# Danger_Shield-v17.net
KiCad netlist of a schematic drawn in EAGLE
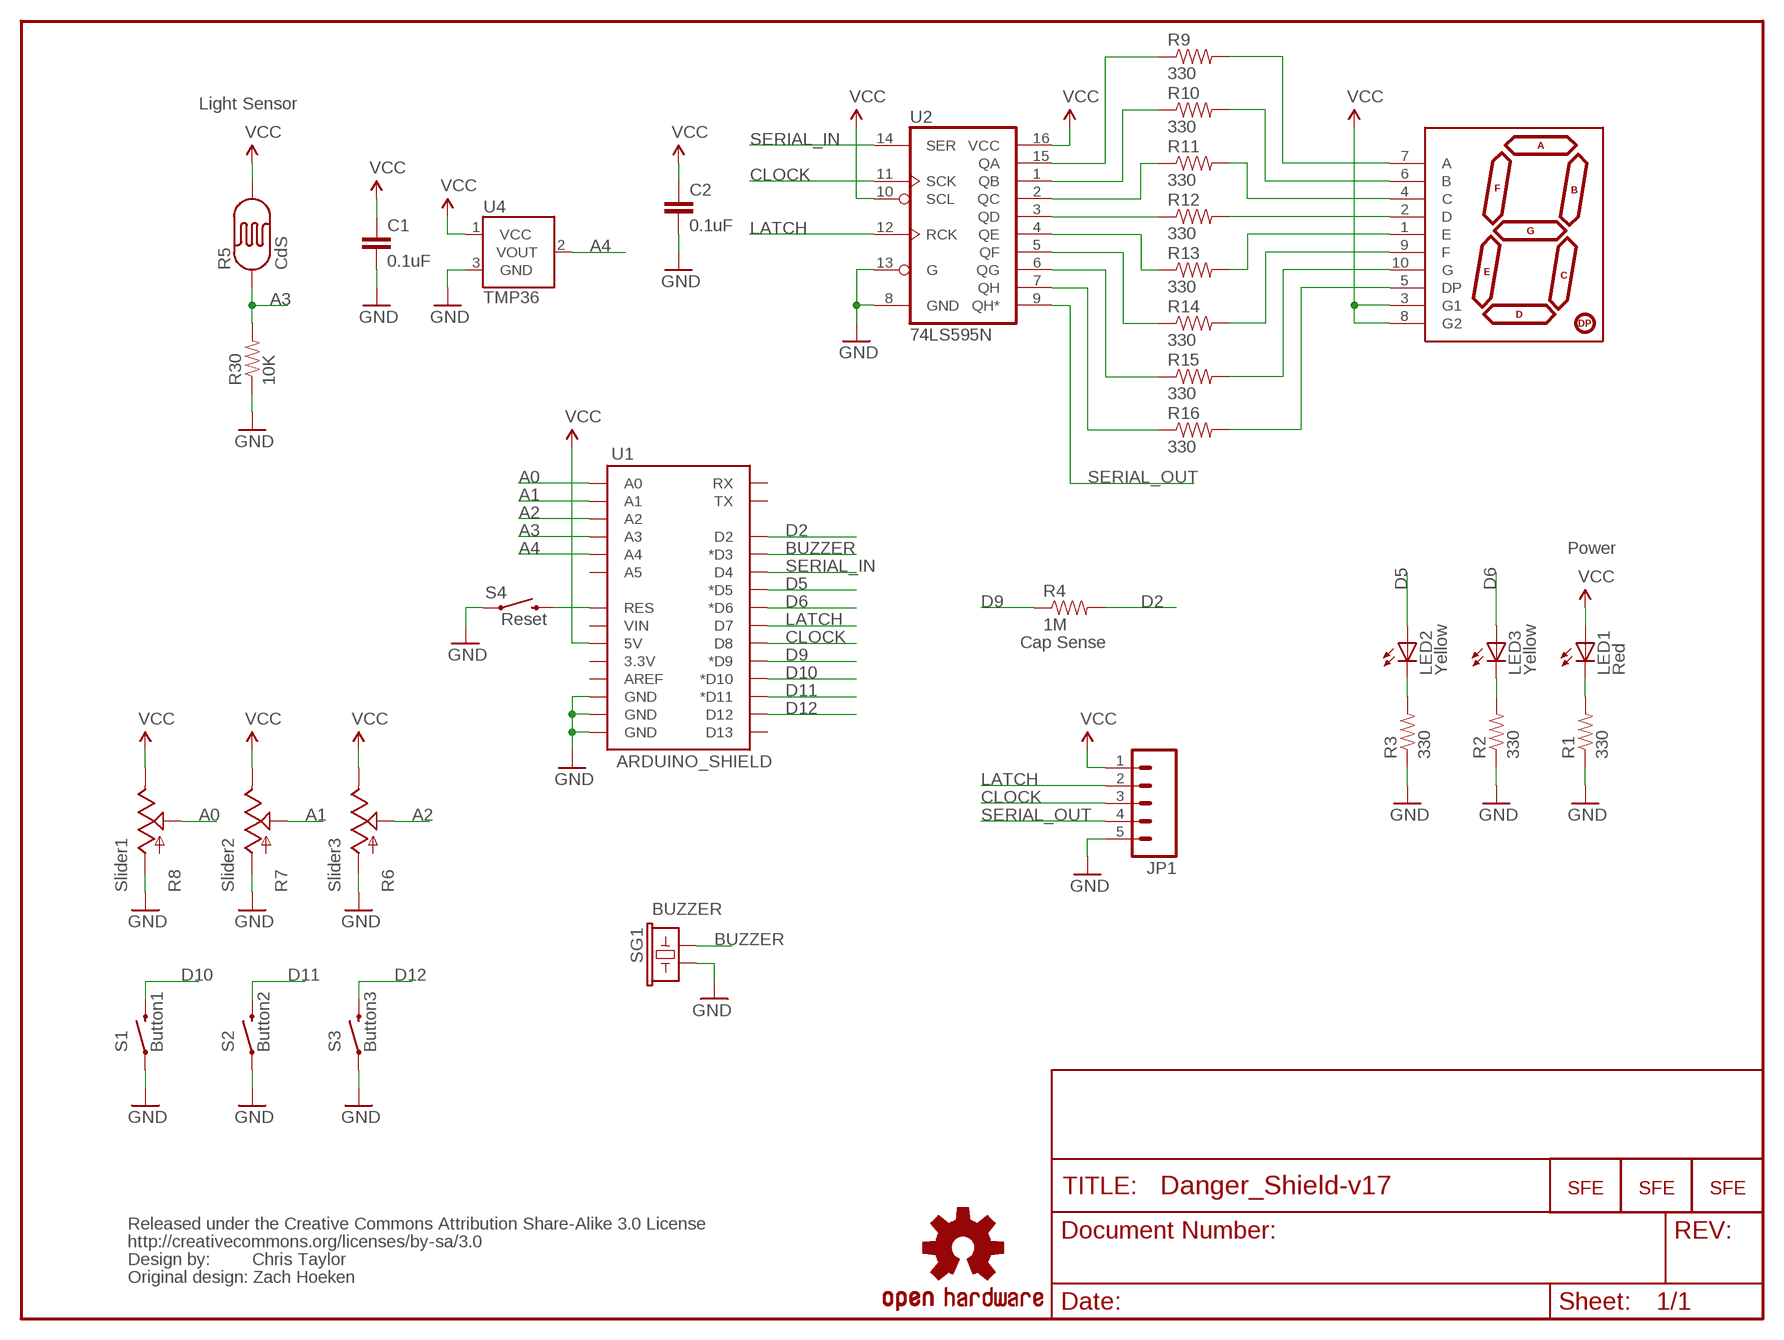
[diagram p0: schematic, sheet 1]

(export (version "E")
  (design (tool "Eeschema 10.0.6"))
  (components
    (comp (ref "C1")
      (value "0.1uF")
      (footprint "eagle-import:CAP-PTH-SMALL2")
      (libsource (lib "eagle-import") (part "CAPPTH2"))
    )
    (comp (ref "C2")
      (value "0.1uF")
      (footprint "eagle-import:CAP-PTH-SMALL2")
      (libsource (lib "eagle-import") (part "CAPPTH2"))
    )
    (comp (ref "JP1")
      (value "M05PTH")
      (footprint "eagle-import:1X05")
      (libsource (lib "eagle-import") (part "M05PTH"))
    )
    (comp (ref "JP2")
      (value "LOGO-SFENEW")
      (footprint "eagle-import:SFE-NEW-WEBLOGO")
      (libsource (lib "eagle-import") (part "LOGO-SFENEW"))
    )
    (comp (ref "JP3")
      (value "LOGO-SFENEW")
      (footprint "eagle-import:SFE-NEW-WEBLOGO")
      (libsource (lib "eagle-import") (part "LOGO-SFENEW"))
    )
    (comp (ref "JP5")
      (value "LOGO-SFESK")
      (footprint "eagle-import:SFE-LOGO-FLAME")
      (libsource (lib "eagle-import") (part "LOGO-SFESK"))
    )
    (comp (ref "LED1")
      (value "Red")
      (footprint "eagle-import:LED5MM")
      (libsource (lib "eagle-import") (part "LED5MM"))
    )
    (comp (ref "LED2")
      (value "Yellow")
      (footprint "eagle-import:LED5MM")
      (libsource (lib "eagle-import") (part "LED5MM"))
    )
    (comp (ref "LED3")
      (value "Yellow")
      (footprint "eagle-import:LED5MM")
      (libsource (lib "eagle-import") (part "LED5MM"))
    )
    (comp (ref "R1")
      (value "330")
      (footprint "eagle-import:AXIAL-0.3")
      (libsource (lib "eagle-import") (part "RESISTORAXIAL-0.3"))
    )
    (comp (ref "R2")
      (value "330")
      (footprint "eagle-import:AXIAL-0.3")
      (libsource (lib "eagle-import") (part "RESISTORAXIAL-0.3"))
    )
    (comp (ref "R3")
      (value "330")
      (footprint "eagle-import:AXIAL-0.3")
      (libsource (lib "eagle-import") (part "RESISTORAXIAL-0.3"))
    )
    (comp (ref "R4")
      (value "1M")
      (footprint "eagle-import:AXIAL-0.3")
      (libsource (lib "eagle-import") (part "RESISTORAXIAL-0.3"))
    )
    (comp (ref "R5")
      (value "CdS")
      (footprint "eagle-import:PHOTOCELL")
      (libsource (lib "eagle-import") (part "PHOTOCELLPTH"))
    )
    (comp (ref "R6")
      (value "Slider3")
      (footprint "eagle-import:SLIDER")
      (libsource (lib "eagle-import") (part "SLIDER"))
    )
    (comp (ref "R7")
      (value "Slider2")
      (footprint "eagle-import:SLIDER")
      (libsource (lib "eagle-import") (part "SLIDER"))
    )
    (comp (ref "R8")
      (value "Slider1")
      (footprint "eagle-import:SLIDER")
      (libsource (lib "eagle-import") (part "SLIDER"))
    )
    (comp (ref "R9")
      (value "330")
      (footprint "eagle-import:AXIAL-0.3")
      (libsource (lib "eagle-import") (part "RESISTORAXIAL-0.3"))
    )
    (comp (ref "R10")
      (value "330")
      (footprint "eagle-import:AXIAL-0.3")
      (libsource (lib "eagle-import") (part "RESISTORAXIAL-0.3"))
    )
    (comp (ref "R11")
      (value "330")
      (footprint "eagle-import:AXIAL-0.3")
      (libsource (lib "eagle-import") (part "RESISTORAXIAL-0.3"))
    )
    (comp (ref "R12")
      (value "330")
      (footprint "eagle-import:AXIAL-0.3")
      (libsource (lib "eagle-import") (part "RESISTORAXIAL-0.3"))
    )
    (comp (ref "R13")
      (value "330")
      (footprint "eagle-import:AXIAL-0.3")
      (libsource (lib "eagle-import") (part "RESISTORAXIAL-0.3"))
    )
    (comp (ref "R14")
      (value "330")
      (footprint "eagle-import:AXIAL-0.3")
      (libsource (lib "eagle-import") (part "RESISTORAXIAL-0.3"))
    )
    (comp (ref "R15")
      (value "330")
      (footprint "eagle-import:AXIAL-0.3")
      (libsource (lib "eagle-import") (part "RESISTORAXIAL-0.3"))
    )
    (comp (ref "R16")
      (value "330")
      (footprint "eagle-import:AXIAL-0.3")
      (libsource (lib "eagle-import") (part "RESISTORAXIAL-0.3"))
    )
    (comp (ref "R30")
      (value "10K")
      (footprint "eagle-import:AXIAL-0.3")
      (libsource (lib "eagle-import") (part "RESISTORAXIAL-0.3"))
    )
    (comp (ref "S1")
      (value "Button1")
      (footprint "eagle-import:TACTILE-PTH-12MM")
      (libsource (lib "eagle-import") (part "SWITCH-MOMENTARY-212MM"))
    )
    (comp (ref "S2")
      (value "Button2")
      (footprint "eagle-import:TACTILE-PTH-12MM")
      (libsource (lib "eagle-import") (part "SWITCH-MOMENTARY-212MM"))
    )
    (comp (ref "S3")
      (value "Button3")
      (footprint "eagle-import:TACTILE-PTH-12MM")
      (libsource (lib "eagle-import") (part "SWITCH-MOMENTARY-212MM"))
    )
    (comp (ref "S4")
      (value "Reset")
      (footprint "eagle-import:TACTILE-PTH")
      (libsource (lib "eagle-import") (part "SWITCH-MOMENTARY-2PTH"))
    )
    (comp (ref "SG1")
      (value "BUZZER")
      (footprint "eagle-import:BUZZER-12MM")
      (libsource (lib "eagle-import") (part "BUZZERPTH"))
    )
    (comp (ref "U$1")
      (value "CREATIVE_COMMONS")
      (footprint "eagle-import:CREATIVE_COMMONS")
      (libsource (lib "eagle-import") (part "CREATIVE_COMMONS"))
    )
    (comp (ref "U$2")
      (value "OSHW-LOGOM")
      (footprint "eagle-import:OSHW-LOGO-M")
      (libsource (lib "eagle-import") (part "OSHW-LOGOM"))
    )
    (comp (ref "U1")
      (value "ARDUINO_SHIELD")
      (footprint "eagle-import:DUEMILANOVE_VIAS")
      (libsource (lib "eagle-import") (part "ARDUINO_SHIELDNO_SILK"))
    )
    (comp (ref "U2")
      (value "74LS595N")
      (footprint "eagle-import:DIL16")
      (libsource (lib "eagle-import") (part "74595NLS"))
    )
    (comp (ref "U4")
      (value "TMP36")
      (footprint "eagle-import:TO-92")
      (libsource (lib "eagle-import") (part "TMP36GT9"))
    )
    (comp (ref "U6")
      (value "7-SEGMENT-DISPLAY-1\"-RED")
      (footprint "eagle-import:7-SEGMENT-1_PTH")
      (libsource (lib "eagle-import") (part "7-SEGMENT-DISPLAY-1{dblquote}-RED"))
    )
  )
  (nets
    (net (code "1") (name "/A0") (class "Default")
      (node (ref "R8") (pin "2A") (pinfunction "S_2A") (pintype "passive"))
      (node (ref "U1") (pin "A0") (pinfunction "A0_A0") (pintype "bidirectional"))
    )
    (net (code "2") (name "/A1") (class "Default")
      (node (ref "R7") (pin "2A") (pinfunction "S_2A") (pintype "passive"))
      (node (ref "U1") (pin "A1") (pinfunction "A1_A1") (pintype "bidirectional"))
    )
    (net (code "3") (name "/A2") (class "Default")
      (node (ref "R6") (pin "2A") (pinfunction "S_2A") (pintype "passive"))
      (node (ref "U1") (pin "A2") (pinfunction "A2_A2") (pintype "bidirectional"))
    )
    (net (code "4") (name "/A3") (class "Default")
      (node (ref "R30") (pin "P$2") (pinfunction "2_P$2") (pintype "passive"))
      (node (ref "R5") (pin "1") (pinfunction "P$1_1") (pintype "bidirectional"))
      (node (ref "U1") (pin "A3") (pinfunction "A3_A3") (pintype "bidirectional"))
    )
    (net (code "5") (name "/A4") (class "Default")
      (node (ref "U1") (pin "A4") (pinfunction "A4_A4") (pintype "bidirectional"))
      (node (ref "U4") (pin "2") (pinfunction "VOUT_2") (pintype "bidirectional"))
    )
    (net (code "6") (name "/BUZZER") (class "Default")
      (node (ref "SG1") (pin "+") (pinfunction "1_+") (pintype "passive"))
      (node (ref "U1") (pin "D3") (pinfunction "*D3_D3") (pintype "bidirectional"))
    )
    (net (code "7") (name "/CLOCK") (class "Default")
      (node (ref "JP1") (pin "3") (pinfunction "3_3") (pintype "passive"))
      (node (ref "U1") (pin "D8") (pinfunction "D8_D8") (pintype "bidirectional"))
      (node (ref "U2") (pin "11") (pinfunction "SCK_11") (pintype "input"))
    )
    (net (code "8") (name "/D2") (class "Default")
      (node (ref "R4") (pin "P$2") (pinfunction "2_P$2") (pintype "passive"))
      (node (ref "U1") (pin "D2") (pinfunction "D2_D2") (pintype "bidirectional"))
    )
    (net (code "9") (name "/D5") (class "Default")
      (node (ref "LED2") (pin "A") (pinfunction "A_A") (pintype "passive"))
      (node (ref "U1") (pin "D5") (pinfunction "*D5_D5") (pintype "bidirectional"))
    )
    (net (code "10") (name "/D6") (class "Default")
      (node (ref "LED3") (pin "A") (pinfunction "A_A") (pintype "passive"))
      (node (ref "U1") (pin "D6") (pinfunction "*D6_D6") (pintype "bidirectional"))
    )
    (net (code "11") (name "/D9") (class "Default")
      (node (ref "R4") (pin "P$1") (pinfunction "1_P$1") (pintype "passive"))
      (node (ref "U1") (pin "D9") (pinfunction "*D9_D9") (pintype "bidirectional"))
    )
    (net (code "12") (name "/D10") (class "Default")
      (node (ref "S1") (pin "3") (pinfunction "2_3") (pintype "passive"))
      (node (ref "U1") (pin "D10") (pinfunction "*D10_D10") (pintype "bidirectional"))
    )
    (net (code "13") (name "/D11") (class "Default")
      (node (ref "S2") (pin "3") (pinfunction "2_3") (pintype "passive"))
      (node (ref "U1") (pin "D11") (pinfunction "*D11_D11") (pintype "bidirectional"))
    )
    (net (code "14") (name "/D12") (class "Default")
      (node (ref "S3") (pin "3") (pinfunction "2_3") (pintype "passive"))
      (node (ref "U1") (pin "D12") (pinfunction "D12_D12") (pintype "bidirectional"))
    )
    (net (code "15") (name "/LATCH") (class "Default")
      (node (ref "JP1") (pin "2") (pinfunction "2_2") (pintype "passive"))
      (node (ref "U1") (pin "D7") (pinfunction "D7_D7") (pintype "bidirectional"))
      (node (ref "U2") (pin "12") (pinfunction "RCK_12") (pintype "input"))
    )
    (net (code "16") (name "/SERIAL_IN") (class "Default")
      (node (ref "U1") (pin "D4") (pinfunction "D4_D4") (pintype "bidirectional"))
      (node (ref "U2") (pin "14") (pinfunction "SER_14") (pintype "input"))
    )
    (net (code "17") (name "/SERIAL_OUT") (class "Default")
      (node (ref "JP1") (pin "4") (pinfunction "4_4") (pintype "passive"))
      (node (ref "U2") (pin "9") (pinfunction "QH*_9") (pintype "tri_state"))
    )
    (net (code "18") (name "GND") (class "Default")
      (node (ref "C1") (pin "2") (pinfunction "2_2") (pintype "passive"))
      (node (ref "C2") (pin "2") (pinfunction "2_2") (pintype "passive"))
      (node (ref "JP1") (pin "5") (pinfunction "5_5") (pintype "passive"))
      (node (ref "R1") (pin "P$1") (pinfunction "1_P$1") (pintype "passive"))
      (node (ref "R2") (pin "P$1") (pinfunction "1_P$1") (pintype "passive"))
      (node (ref "R3") (pin "P$1") (pinfunction "1_P$1") (pintype "passive"))
      (node (ref "R30") (pin "P$1") (pinfunction "1_P$1") (pintype "passive"))
      (node (ref "R6") (pin "3") (pinfunction "A_3") (pintype "passive"))
      (node (ref "R7") (pin "3") (pinfunction "A_3") (pintype "passive"))
      (node (ref "R8") (pin "3") (pinfunction "A_3") (pintype "passive"))
      (node (ref "S1") (pin "1") (pinfunction "1_1") (pintype "passive"))
      (node (ref "S2") (pin "1") (pinfunction "1_1") (pintype "passive"))
      (node (ref "S3") (pin "1") (pinfunction "1_1") (pintype "passive"))
      (node (ref "S4") (pin "1") (pinfunction "1_1") (pintype "passive"))
      (node (ref "SG1") (pin "-") (pinfunction "2_-") (pintype "passive"))
      (node (ref "U1") (pin "GND@0") (pinfunction "GND_GND@0") (pintype "bidirectional"))
      (node (ref "U1") (pin "GND@1") (pinfunction "GND_GND@1") (pintype "bidirectional"))
      (node (ref "U1") (pin "GND@2") (pinfunction "GND_GND@2") (pintype "bidirectional"))
      (node (ref "U2") (pin "13") (pinfunction "G_13") (pintype "input"))
      (node (ref "U2") (pin "8") (pinfunction "GND_8") (pintype "power_in"))
      (node (ref "U4") (pin "3") (pinfunction "GND_3") (pintype "bidirectional"))
    )
    (net (code "19") (name "Net-(LED1-C)") (class "Default")
      (node (ref "LED1") (pin "K") (pinfunction "C_K") (pintype "passive"))
      (node (ref "R1") (pin "P$2") (pinfunction "2_P$2") (pintype "passive"))
    )
    (net (code "20") (name "Net-(LED2-C)") (class "Default")
      (node (ref "LED2") (pin "K") (pinfunction "C_K") (pintype "passive"))
      (node (ref "R3") (pin "P$2") (pinfunction "2_P$2") (pintype "passive"))
    )
    (net (code "21") (name "Net-(LED3-C)") (class "Default")
      (node (ref "LED3") (pin "K") (pinfunction "C_K") (pintype "passive"))
      (node (ref "R2") (pin "P$2") (pinfunction "2_P$2") (pintype "passive"))
    )
    (net (code "22") (name "Net-(R9-1)") (class "Default")
      (node (ref "R9") (pin "P$1") (pinfunction "1_P$1") (pintype "passive"))
      (node (ref "U2") (pin "15") (pinfunction "QA_15") (pintype "tri_state"))
    )
    (net (code "23") (name "Net-(R9-2)") (class "Default")
      (node (ref "R9") (pin "P$2") (pinfunction "2_P$2") (pintype "passive"))
      (node (ref "U6") (pin "7") (pinfunction "A_7") (pintype "bidirectional"))
    )
    (net (code "24") (name "Net-(R10-1)") (class "Default")
      (node (ref "R10") (pin "P$1") (pinfunction "1_P$1") (pintype "passive"))
      (node (ref "U2") (pin "1") (pinfunction "QB_1") (pintype "tri_state"))
    )
    (net (code "25") (name "Net-(R10-2)") (class "Default")
      (node (ref "R10") (pin "P$2") (pinfunction "2_P$2") (pintype "passive"))
      (node (ref "U6") (pin "6") (pinfunction "B_6") (pintype "bidirectional"))
    )
    (net (code "26") (name "Net-(R11-1)") (class "Default")
      (node (ref "R11") (pin "P$1") (pinfunction "1_P$1") (pintype "passive"))
      (node (ref "U2") (pin "2") (pinfunction "QC_2") (pintype "tri_state"))
    )
    (net (code "27") (name "Net-(R11-2)") (class "Default")
      (node (ref "R11") (pin "P$2") (pinfunction "2_P$2") (pintype "passive"))
      (node (ref "U6") (pin "4") (pinfunction "C_4") (pintype "bidirectional"))
    )
    (net (code "28") (name "Net-(R12-1)") (class "Default")
      (node (ref "R12") (pin "P$1") (pinfunction "1_P$1") (pintype "passive"))
      (node (ref "U2") (pin "3") (pinfunction "QD_3") (pintype "tri_state"))
    )
    (net (code "29") (name "Net-(R12-2)") (class "Default")
      (node (ref "R12") (pin "P$2") (pinfunction "2_P$2") (pintype "passive"))
      (node (ref "U6") (pin "2") (pinfunction "D_2") (pintype "bidirectional"))
    )
    (net (code "30") (name "Net-(R13-1)") (class "Default")
      (node (ref "R13") (pin "P$1") (pinfunction "1_P$1") (pintype "passive"))
      (node (ref "U2") (pin "4") (pinfunction "QE_4") (pintype "tri_state"))
    )
    (net (code "31") (name "Net-(R13-2)") (class "Default")
      (node (ref "R13") (pin "P$2") (pinfunction "2_P$2") (pintype "passive"))
      (node (ref "U6") (pin "1") (pinfunction "E_1") (pintype "bidirectional"))
    )
    (net (code "32") (name "Net-(R14-1)") (class "Default")
      (node (ref "R14") (pin "P$1") (pinfunction "1_P$1") (pintype "passive"))
      (node (ref "U2") (pin "5") (pinfunction "QF_5") (pintype "tri_state"))
    )
    (net (code "33") (name "Net-(R14-2)") (class "Default")
      (node (ref "R14") (pin "P$2") (pinfunction "2_P$2") (pintype "passive"))
      (node (ref "U6") (pin "9") (pinfunction "F_9") (pintype "bidirectional"))
    )
    (net (code "34") (name "Net-(R15-1)") (class "Default")
      (node (ref "R15") (pin "P$1") (pinfunction "1_P$1") (pintype "passive"))
      (node (ref "U2") (pin "6") (pinfunction "QG_6") (pintype "tri_state"))
    )
    (net (code "35") (name "Net-(R15-2)") (class "Default")
      (node (ref "R15") (pin "P$2") (pinfunction "2_P$2") (pintype "passive"))
      (node (ref "U6") (pin "10") (pinfunction "G_10") (pintype "bidirectional"))
    )
    (net (code "36") (name "Net-(R16-1)") (class "Default")
      (node (ref "R16") (pin "P$1") (pinfunction "1_P$1") (pintype "passive"))
      (node (ref "U2") (pin "7") (pinfunction "QH_7") (pintype "tri_state"))
    )
    (net (code "37") (name "Net-(R16-2)") (class "Default")
      (node (ref "R16") (pin "P$2") (pinfunction "2_P$2") (pintype "passive"))
      (node (ref "U6") (pin "5") (pinfunction "DP_5") (pintype "bidirectional"))
    )
    (net (code "38") (name "Net-(S4-2)") (class "Default")
      (node (ref "S4") (pin "3") (pinfunction "2_3") (pintype "passive"))
      (node (ref "U1") (pin "RES") (pinfunction "RES_RES") (pintype "bidirectional"))
    )
    (net (code "39") (name "VCC") (class "Default")
      (node (ref "C1") (pin "1") (pinfunction "1_1") (pintype "passive"))
      (node (ref "C2") (pin "1") (pinfunction "1_1") (pintype "passive"))
      (node (ref "JP1") (pin "1") (pinfunction "1_1") (pintype "passive"))
      (node (ref "LED1") (pin "A") (pinfunction "A_A") (pintype "passive"))
      (node (ref "R5") (pin "2") (pinfunction "P$2_2") (pintype "bidirectional"))
      (node (ref "R6") (pin "1") (pinfunction "E_1") (pintype "passive"))
      (node (ref "R7") (pin "1") (pinfunction "E_1") (pintype "passive"))
      (node (ref "R8") (pin "1") (pinfunction "E_1") (pintype "passive"))
      (node (ref "U1") (pin "5V") (pinfunction "5V_5V") (pintype "bidirectional"))
      (node (ref "U2") (pin "10") (pinfunction "SCL_10") (pintype "input"))
      (node (ref "U2") (pin "16") (pinfunction "VCC_16") (pintype "power_in"))
      (node (ref "U4") (pin "1") (pinfunction "VCC_1") (pintype "bidirectional"))
      (node (ref "U6") (pin "3") (pinfunction "G1_3") (pintype "bidirectional"))
      (node (ref "U6") (pin "8") (pinfunction "G2_8") (pintype "bidirectional"))
    )
    (net (code "40") (name "unconnected-(U1-Pad3.3V)") (class "Default")
      (node (ref "U1") (pin "3.3V") (pinfunction "3.3V_3.3V") (pintype "bidirectional"))
    )
    (net (code "41") (name "unconnected-(U1-PadA5)") (class "Default")
      (node (ref "U1") (pin "A5") (pinfunction "A5_A5") (pintype "bidirectional"))
    )
    (net (code "42") (name "unconnected-(U1-PadAREF)") (class "Default")
      (node (ref "U1") (pin "AREF") (pinfunction "AREF_AREF") (pintype "bidirectional"))
    )
    (net (code "43") (name "unconnected-(U1-PadD13)") (class "Default")
      (node (ref "U1") (pin "D13") (pinfunction "D13_D13") (pintype "bidirectional"))
    )
    (net (code "44") (name "unconnected-(U1-PadRX)") (class "Default")
      (node (ref "U1") (pin "RX") (pinfunction "RX_RX") (pintype "bidirectional"))
    )
    (net (code "45") (name "unconnected-(U1-PadTX)") (class "Default")
      (node (ref "U1") (pin "TX") (pinfunction "TX_TX") (pintype "bidirectional"))
    )
    (net (code "46") (name "unconnected-(U1-PadVIN)") (class "Default")
      (node (ref "U1") (pin "VIN") (pinfunction "VIN_VIN") (pintype "bidirectional"))
    )
  )
)
